# tama.net
KiCad netlist of a schematic drawn in EAGLE
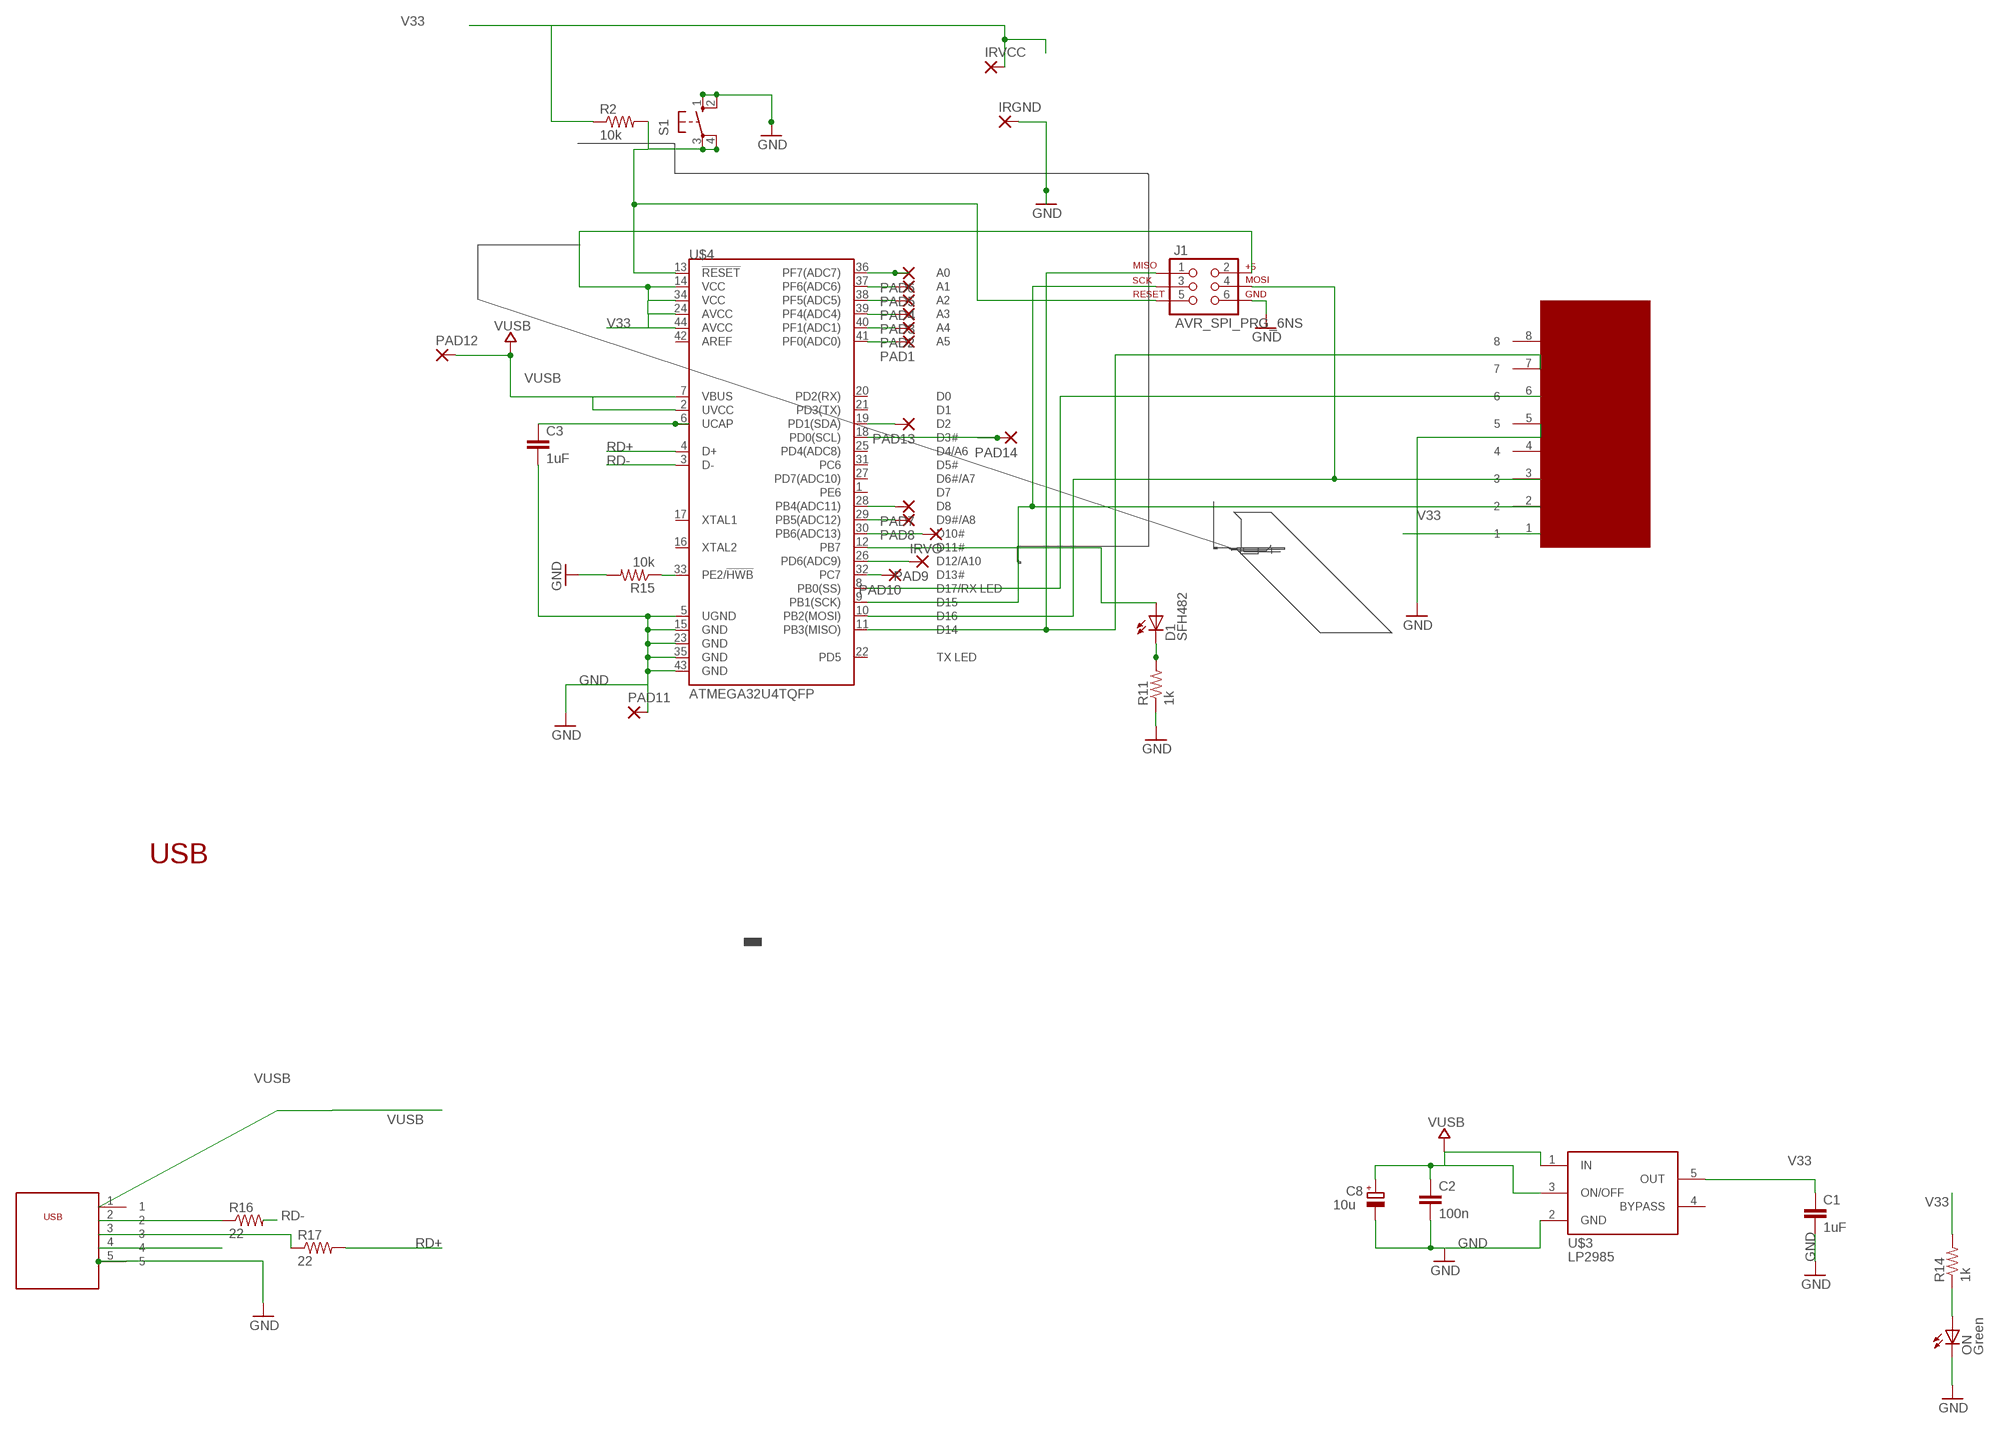
[diagram p0: schematic, sheet 1]

(export (version "E")
  (design (tool "Eeschema 10.0.6"))
  (components
    (comp (ref "C1")
      (value "1uF")
      (footprint "eagle-import:C1206")
      (libsource (lib "eagle-import") (part "C-EUC1206"))
    )
    (comp (ref "C2")
      (value "100n")
      (footprint "eagle-import:C1206")
      (libsource (lib "eagle-import") (part "C-EUC1206"))
    )
    (comp (ref "C3")
      (value "1uF")
      (footprint "eagle-import:C1206")
      (libsource (lib "eagle-import") (part "C-EUC1206"))
    )
    (comp (ref "C8")
      (value "10u")
      (footprint "eagle-import:SMC_B")
      (libsource (lib "eagle-import") (part "CPOL-EUSMCB"))
    )
    (comp (ref "D1")
      (value "SFH482")
      (footprint "eagle-import:SFH482")
      (libsource (lib "eagle-import") (part "SFH482"))
    )
    (comp (ref "IRGND")
      (value "2,15/1,0")
      (footprint "eagle-import:2,15_1,0")
      (libsource (lib "eagle-import") (part "2,15/1,0"))
    )
    (comp (ref "IRVCC")
      (value "2,15/1,0")
      (footprint "eagle-import:2,15_1,0")
      (libsource (lib "eagle-import") (part "2,15/1,0"))
    )
    (comp (ref "IRVO")
      (value "2,15/1,0")
      (footprint "eagle-import:2,15_1,0")
      (libsource (lib "eagle-import") (part "2,15/1,0"))
    )
    (comp (ref "J1")
      (value "AVR_SPI_PRG_6NS")
      (footprint "eagle-import:2X3-NS")
      (libsource (lib "eagle-import") (part "AVR_SPI_PRG_6NS"))
    )
    (comp (ref "ON")
      (value "Green")
      (footprint "eagle-import:CHIPLED_0805")
      (libsource (lib "eagle-import") (part "LEDCHIPLED_0805"))
    )
    (comp (ref "PAD1")
      (value "2,54/0,8")
      (footprint "eagle-import:2,54_0,8")
      (libsource (lib "eagle-import") (part "2,54/0,8"))
    )
    (comp (ref "PAD2")
      (value "2,54/0,8")
      (footprint "eagle-import:2,54_0,8")
      (libsource (lib "eagle-import") (part "2,54/0,8"))
    )
    (comp (ref "PAD3")
      (value "2,54/0,8")
      (footprint "eagle-import:2,54_0,8")
      (libsource (lib "eagle-import") (part "2,54/0,8"))
    )
    (comp (ref "PAD4")
      (value "2,54/0,8")
      (footprint "eagle-import:2,54_0,8")
      (libsource (lib "eagle-import") (part "2,54/0,8"))
    )
    (comp (ref "PAD5")
      (value "2,54/0,8")
      (footprint "eagle-import:2,54_0,8")
      (libsource (lib "eagle-import") (part "2,54/0,8"))
    )
    (comp (ref "PAD6")
      (value "2,54/0,8")
      (footprint "eagle-import:2,54_0,8")
      (libsource (lib "eagle-import") (part "2,54/0,8"))
    )
    (comp (ref "PAD7")
      (value "2,54/0,8")
      (footprint "eagle-import:2,54_0,8")
      (libsource (lib "eagle-import") (part "2,54/0,8"))
    )
    (comp (ref "PAD8")
      (value "2,54/0,8")
      (footprint "eagle-import:2,54_0,8")
      (libsource (lib "eagle-import") (part "2,54/0,8"))
    )
    (comp (ref "PAD9")
      (value "2,54/0,8")
      (footprint "eagle-import:2,54_0,8")
      (libsource (lib "eagle-import") (part "2,54/0,8"))
    )
    (comp (ref "PAD10")
      (value "2,54/0,8")
      (footprint "eagle-import:2,54_0,8")
      (libsource (lib "eagle-import") (part "2,54/0,8"))
    )
    (comp (ref "PAD11")
      (value "2,54/0,8")
      (footprint "eagle-import:2,54_0,8")
      (libsource (lib "eagle-import") (part "2,54/0,8"))
    )
    (comp (ref "PAD12")
      (value "2,54/0,8")
      (footprint "eagle-import:2,54_0,8")
      (libsource (lib "eagle-import") (part "2,54/0,8"))
    )
    (comp (ref "PAD13")
      (value "2,54/0,8")
      (footprint "eagle-import:2,54_0,8")
      (libsource (lib "eagle-import") (part "2,54/0,8"))
    )
    (comp (ref "PAD14")
      (value "2,54/0,8")
      (footprint "eagle-import:2,54_0,8")
      (libsource (lib "eagle-import") (part "2,54/0,8"))
    )
    (comp (ref "R2")
      (value "10k")
      (footprint "eagle-import:R1206W")
      (libsource (lib "eagle-import") (part "R-US_R1206W"))
    )
    (comp (ref "R11")
      (value "1k")
      (footprint "eagle-import:R1206")
      (libsource (lib "eagle-import") (part "R-US_R1206"))
    )
    (comp (ref "R14")
      (value "1k")
      (footprint "eagle-import:R1206")
      (libsource (lib "eagle-import") (part "R-US_R1206"))
    )
    (comp (ref "R15")
      (value "10k")
      (footprint "eagle-import:R1206")
      (libsource (lib "eagle-import") (part "R-US_R1206"))
    )
    (comp (ref "R16")
      (value "22")
      (footprint "eagle-import:R1206")
      (libsource (lib "eagle-import") (part "R-US_R1206"))
    )
    (comp (ref "R17")
      (value "22")
      (footprint "eagle-import:R1206")
      (libsource (lib "eagle-import") (part "R-US_R1206"))
    )
    (comp (ref "S1")
      (value "10-XX")
      (footprint "eagle-import:B3F-10XX")
      (fields (field (name "MPN") "B3F-1000"))
      (libsource (lib "eagle-import") (part "10-XX"))
    )
    (comp (ref "U$1")
      (value "TAMA")
      (footprint "eagle-import:TAMACONTACT")
      (libsource (lib "eagle-import") (part "TAMA"))
    )
    (comp (ref "U$2")
      (value "USB")
      (footprint "eagle-import:USB")
      (libsource (lib "eagle-import") (part "USB"))
    )
    (comp (ref "U$3")
      (value "LP2985")
      (footprint "eagle-import:SOT23-5")
      (libsource (lib "eagle-import") (part "LP2985"))
    )
    (comp (ref "U$4")
      (value "ATMEGA32U4TQFP")
      (footprint "eagle-import:SPARKFUN-DIGITALIC_TQFP44")
      (libsource (lib "eagle-import") (part "ATMEGA32U4TQFP"))
    )
  )
  (nets
    (net (code "1") (name "/RD+") (class "Default")
      (node (ref "R17") (pin "2") (pinfunction "2_2") (pintype "passive"))
      (node (ref "U$4") (pin "4") (pinfunction "D+_4") (pintype "bidirectional"))
    )
    (net (code "2") (name "/RD-") (class "Default")
      (node (ref "R16") (pin "2") (pinfunction "2_2") (pintype "passive"))
      (node (ref "U$4") (pin "3") (pinfunction "D-_3") (pintype "bidirectional"))
    )
    (net (code "3") (name "/V33") (class "Default")
      (node (ref "C1") (pin "1") (pinfunction "1_1") (pintype "passive"))
      (node (ref "IRVCC") (pin "1") (pinfunction "P_1") (pintype "passive"))
      (node (ref "J1") (pin "2") (pinfunction "2_2") (pintype "passive"))
      (node (ref "R14") (pin "2") (pinfunction "2_2") (pintype "passive"))
      (node (ref "R2") (pin "1") (pinfunction "1_1") (pintype "passive"))
      (node (ref "U$1") (pin "1") (pinfunction "1_1") (pintype "bidirectional"))
      (node (ref "U$3") (pin "5") (pinfunction "OUT_5") (pintype "bidirectional"))
      (node (ref "U$4") (pin "14") (pinfunction "VCC_14") (pintype "bidirectional"))
      (node (ref "U$4") (pin "24") (pinfunction "AVCC_24") (pintype "bidirectional"))
      (node (ref "U$4") (pin "34") (pinfunction "VCC_34") (pintype "bidirectional"))
      (node (ref "U$4") (pin "44") (pinfunction "AVCC_44") (pintype "bidirectional"))
    )
    (net (code "4") (name "GND") (class "Default")
      (node (ref "C1") (pin "2") (pinfunction "2_2") (pintype "passive"))
      (node (ref "C2") (pin "2") (pinfunction "2_2") (pintype "passive"))
      (node (ref "C3") (pin "2") (pinfunction "2_2") (pintype "passive"))
      (node (ref "C8") (pin "-") (pinfunction "-_-") (pintype "passive"))
      (node (ref "IRGND") (pin "1") (pinfunction "P_1") (pintype "passive"))
      (node (ref "J1") (pin "6") (pinfunction "6_6") (pintype "passive"))
      (node (ref "ON") (pin "C") (pinfunction "C_C") (pintype "passive"))
      (node (ref "PAD11") (pin "1") (pinfunction "P_1") (pintype "passive"))
      (node (ref "R11") (pin "1") (pinfunction "1_1") (pintype "passive"))
      (node (ref "R15") (pin "2") (pinfunction "2_2") (pintype "passive"))
      (node (ref "S1") (pin "1") (pinfunction "S_1") (pintype "passive"))
      (node (ref "S1") (pin "2") (pinfunction "S1_2") (pintype "passive"))
      (node (ref "U$1") (pin "5") (pinfunction "5_5") (pintype "bidirectional"))
      (node (ref "U$2") (pin "5") (pinfunction "5_5") (pintype "bidirectional"))
      (node (ref "U$3") (pin "2") (pinfunction "GND_2") (pintype "bidirectional"))
      (node (ref "U$4") (pin "15") (pinfunction "GND_15") (pintype "bidirectional"))
      (node (ref "U$4") (pin "23") (pinfunction "GND_23") (pintype "bidirectional"))
      (node (ref "U$4") (pin "35") (pinfunction "GND_35") (pintype "bidirectional"))
      (node (ref "U$4") (pin "43") (pinfunction "GND_43") (pintype "bidirectional"))
      (node (ref "U$4") (pin "5") (pinfunction "UGND_5") (pintype "bidirectional"))
    )
    (net (code "5") (name "Net-(D1-C)") (class "Default")
      (node (ref "D1") (pin "K") (pinfunction "C_K") (pintype "passive"))
      (node (ref "R11") (pin "2") (pinfunction "2_2") (pintype "passive"))
    )
    (net (code "6") (name "Net-(IRVO-P)") (class "Default")
      (node (ref "IRVO") (pin "1") (pinfunction "P_1") (pintype "passive"))
      (node (ref "U$4") (pin "30") (pinfunction "PB6(ADC13)_30") (pintype "bidirectional"))
    )
    (net (code "7") (name "Net-(ON-PadA)") (class "Default")
      (node (ref "ON") (pin "A") (pinfunction "A_A") (pintype "passive"))
      (node (ref "R14") (pin "1") (pinfunction "1_1") (pintype "passive"))
    )
    (net (code "8") (name "Net-(PAD1-P)") (class "Default")
      (node (ref "PAD1") (pin "1") (pinfunction "P_1") (pintype "passive"))
      (node (ref "U$4") (pin "41") (pinfunction "PF0(ADC0)_41") (pintype "bidirectional"))
    )
    (net (code "9") (name "Net-(PAD2-P)") (class "Default")
      (node (ref "PAD2") (pin "1") (pinfunction "P_1") (pintype "passive"))
      (node (ref "U$4") (pin "40") (pinfunction "PF1(ADC1)_40") (pintype "bidirectional"))
    )
    (net (code "10") (name "Net-(PAD3-P)") (class "Default")
      (node (ref "PAD3") (pin "1") (pinfunction "P_1") (pintype "passive"))
      (node (ref "U$4") (pin "39") (pinfunction "PF4(ADC4)_39") (pintype "bidirectional"))
    )
    (net (code "11") (name "Net-(PAD4-P)") (class "Default")
      (node (ref "PAD4") (pin "1") (pinfunction "P_1") (pintype "passive"))
      (node (ref "U$4") (pin "38") (pinfunction "PF5(ADC5)_38") (pintype "bidirectional"))
    )
    (net (code "12") (name "Net-(PAD5-P)") (class "Default")
      (node (ref "PAD5") (pin "1") (pinfunction "P_1") (pintype "passive"))
      (node (ref "U$4") (pin "37") (pinfunction "PF6(ADC6)_37") (pintype "bidirectional"))
    )
    (net (code "13") (name "Net-(PAD6-P)") (class "Default")
      (node (ref "PAD6") (pin "1") (pinfunction "P_1") (pintype "passive"))
      (node (ref "U$4") (pin "36") (pinfunction "PF7(ADC7)_36") (pintype "bidirectional"))
    )
    (net (code "14") (name "Net-(PAD7-P)") (class "Default")
      (node (ref "PAD7") (pin "1") (pinfunction "P_1") (pintype "passive"))
      (node (ref "U$4") (pin "28") (pinfunction "PB4(ADC11)_28") (pintype "bidirectional"))
    )
    (net (code "15") (name "Net-(PAD8-P)") (class "Default")
      (node (ref "PAD8") (pin "1") (pinfunction "P_1") (pintype "passive"))
      (node (ref "U$4") (pin "29") (pinfunction "PB5(ADC12)_29") (pintype "bidirectional"))
    )
    (net (code "16") (name "Net-(PAD9-P)") (class "Default")
      (node (ref "PAD9") (pin "1") (pinfunction "P_1") (pintype "passive"))
      (node (ref "U$4") (pin "26") (pinfunction "PD6(ADC9)_26") (pintype "bidirectional"))
    )
    (net (code "17") (name "Net-(PAD10-P)") (class "Default")
      (node (ref "PAD10") (pin "1") (pinfunction "P_1") (pintype "passive"))
      (node (ref "U$4") (pin "32") (pinfunction "PC7_32") (pintype "bidirectional"))
    )
    (net (code "18") (name "Net-(PAD13-P)") (class "Default")
      (node (ref "PAD13") (pin "1") (pinfunction "P_1") (pintype "passive"))
      (node (ref "U$4") (pin "19") (pinfunction "PD1(SDA)_19") (pintype "bidirectional"))
    )
    (net (code "19") (name "Net-(PAD14-P)") (class "Default")
      (node (ref "PAD14") (pin "1") (pinfunction "P_1") (pintype "passive"))
      (node (ref "U$4") (pin "18") (pinfunction "PD0(SCL)_18") (pintype "bidirectional"))
    )
    (net (code "20") (name "Net-(R16-Pad1)") (class "Default")
      (node (ref "R16") (pin "1") (pinfunction "1_1") (pintype "passive"))
      (node (ref "U$2") (pin "2") (pinfunction "2_2") (pintype "bidirectional"))
    )
    (net (code "21") (name "Net-(R17-Pad1)") (class "Default")
      (node (ref "R17") (pin "1") (pinfunction "1_1") (pintype "passive"))
      (node (ref "U$2") (pin "3") (pinfunction "3_3") (pintype "bidirectional"))
    )
    (net (code "22") (name "Net-(S1-P)") (class "Default")
      (node (ref "J1") (pin "5") (pinfunction "5_5") (pintype "passive"))
      (node (ref "R2") (pin "2") (pinfunction "2_2") (pintype "passive"))
      (node (ref "S1") (pin "3") (pinfunction "P_3") (pintype "passive"))
      (node (ref "S1") (pin "4") (pinfunction "P1_4") (pintype "passive"))
      (node (ref "U$4") (pin "13") (pinfunction "~{RESET}_13") (pintype "bidirectional"))
    )
    (net (code "23") (name "Net-(U$4-PB0(SS))") (class "Default")
      (node (ref "U$1") (pin "6") (pinfunction "6_6") (pintype "bidirectional"))
      (node (ref "U$4") (pin "8") (pinfunction "PB0(SS)_8") (pintype "bidirectional"))
    )
    (net (code "24") (name "Net-(U$4-PB1(SCK))") (class "Default")
      (node (ref "J1") (pin "3") (pinfunction "3_3") (pintype "passive"))
      (node (ref "U$1") (pin "2") (pinfunction "2_2") (pintype "bidirectional"))
      (node (ref "U$4") (pin "9") (pinfunction "PB1(SCK)_9") (pintype "bidirectional"))
    )
    (net (code "25") (name "Net-(U$4-PB2(MOSI))") (class "Default")
      (node (ref "J1") (pin "4") (pinfunction "4_4") (pintype "passive"))
      (node (ref "U$1") (pin "3") (pinfunction "3_3") (pintype "bidirectional"))
      (node (ref "U$4") (pin "10") (pinfunction "PB2(MOSI)_10") (pintype "bidirectional"))
    )
    (net (code "26") (name "Net-(U$4-PB3(MISO))") (class "Default")
      (node (ref "J1") (pin "1") (pinfunction "1_1") (pintype "passive"))
      (node (ref "U$1") (pin "7") (pinfunction "7_7") (pintype "bidirectional"))
      (node (ref "U$4") (pin "11") (pinfunction "PB3(MISO)_11") (pintype "bidirectional"))
    )
    (net (code "27") (name "Net-(U$4-PB7)") (class "Default")
      (node (ref "D1") (pin "A") (pinfunction "A_A") (pintype "passive"))
      (node (ref "U$4") (pin "12") (pinfunction "PB7_12") (pintype "bidirectional"))
    )
    (net (code "28") (name "Net-(U$4-PE2{slash}~{HWB})") (class "Default")
      (node (ref "R15") (pin "1") (pinfunction "1_1") (pintype "passive"))
      (node (ref "U$4") (pin "33") (pinfunction "PE2/~{HWB}_33") (pintype "bidirectional"))
    )
    (net (code "29") (name "Net-(U$4-UCAP)") (class "Default")
      (node (ref "C3") (pin "1") (pinfunction "1_1") (pintype "passive"))
      (node (ref "U$4") (pin "6") (pinfunction "UCAP_6") (pintype "bidirectional"))
    )
    (net (code "30") (name "VUSB") (class "Default")
      (node (ref "C2") (pin "1") (pinfunction "1_1") (pintype "passive"))
      (node (ref "C8") (pin "+") (pinfunction "+_+") (pintype "passive"))
      (node (ref "PAD12") (pin "1") (pinfunction "P_1") (pintype "passive"))
      (node (ref "U$2") (pin "1") (pinfunction "1_1") (pintype "bidirectional"))
      (node (ref "U$3") (pin "1") (pinfunction "IN_1") (pintype "bidirectional"))
      (node (ref "U$3") (pin "3") (pinfunction "ON/OFF_3") (pintype "bidirectional"))
      (node (ref "U$4") (pin "2") (pinfunction "UVCC_2") (pintype "bidirectional"))
      (node (ref "U$4") (pin "7") (pinfunction "VBUS_7") (pintype "bidirectional"))
    )
    (net (code "31") (name "unconnected-(U$1-Pad4)") (class "Default")
      (node (ref "U$1") (pin "4") (pinfunction "4_4") (pintype "bidirectional"))
    )
    (net (code "32") (name "unconnected-(U$1-Pad8)") (class "Default")
      (node (ref "U$1") (pin "8") (pinfunction "8_8") (pintype "bidirectional"))
    )
    (net (code "33") (name "unconnected-(U$2-Pad4)") (class "Default")
      (node (ref "U$2") (pin "4") (pinfunction "4_4") (pintype "bidirectional"))
    )
    (net (code "34") (name "unconnected-(U$3-BYPASS-Pad4)") (class "Default")
      (node (ref "U$3") (pin "4") (pinfunction "BYPASS_4") (pintype "bidirectional"))
    )
    (net (code "35") (name "unconnected-(U$4-AREF-Pad42)") (class "Default")
      (node (ref "U$4") (pin "42") (pinfunction "AREF_42") (pintype "bidirectional"))
    )
    (net (code "36") (name "unconnected-(U$4-PC6-Pad31)") (class "Default")
      (node (ref "U$4") (pin "31") (pinfunction "PC6_31") (pintype "bidirectional"))
    )
    (net (code "37") (name "unconnected-(U$4-PD2(RX)-Pad20)") (class "Default")
      (node (ref "U$4") (pin "20") (pinfunction "PD2(RX)_20") (pintype "bidirectional"))
    )
    (net (code "38") (name "unconnected-(U$4-PD3(TX)-Pad21)") (class "Default")
      (node (ref "U$4") (pin "21") (pinfunction "PD3(TX)_21") (pintype "bidirectional"))
    )
    (net (code "39") (name "unconnected-(U$4-PD4(ADC8)-Pad25)") (class "Default")
      (node (ref "U$4") (pin "25") (pinfunction "PD4(ADC8)_25") (pintype "bidirectional"))
    )
    (net (code "40") (name "unconnected-(U$4-PD5-Pad22)") (class "Default")
      (node (ref "U$4") (pin "22") (pinfunction "PD5_22") (pintype "bidirectional"))
    )
    (net (code "41") (name "unconnected-(U$4-PD7(ADC10)-Pad27)") (class "Default")
      (node (ref "U$4") (pin "27") (pinfunction "PD7(ADC10)_27") (pintype "bidirectional"))
    )
    (net (code "42") (name "unconnected-(U$4-PE6-Pad1)") (class "Default")
      (node (ref "U$4") (pin "1") (pinfunction "PE6_1") (pintype "bidirectional"))
    )
    (net (code "43") (name "unconnected-(U$4-XTAL1-Pad17)") (class "Default")
      (node (ref "U$4") (pin "17") (pinfunction "XTAL1_17") (pintype "bidirectional"))
    )
    (net (code "44") (name "unconnected-(U$4-XTAL2-Pad16)") (class "Default")
      (node (ref "U$4") (pin "16") (pinfunction "XTAL2_16") (pintype "bidirectional"))
    )
  )
)
